# SCH_Hollowed_2025-01-09.net
KiCad netlist of a schematic drawn in EasyEDA
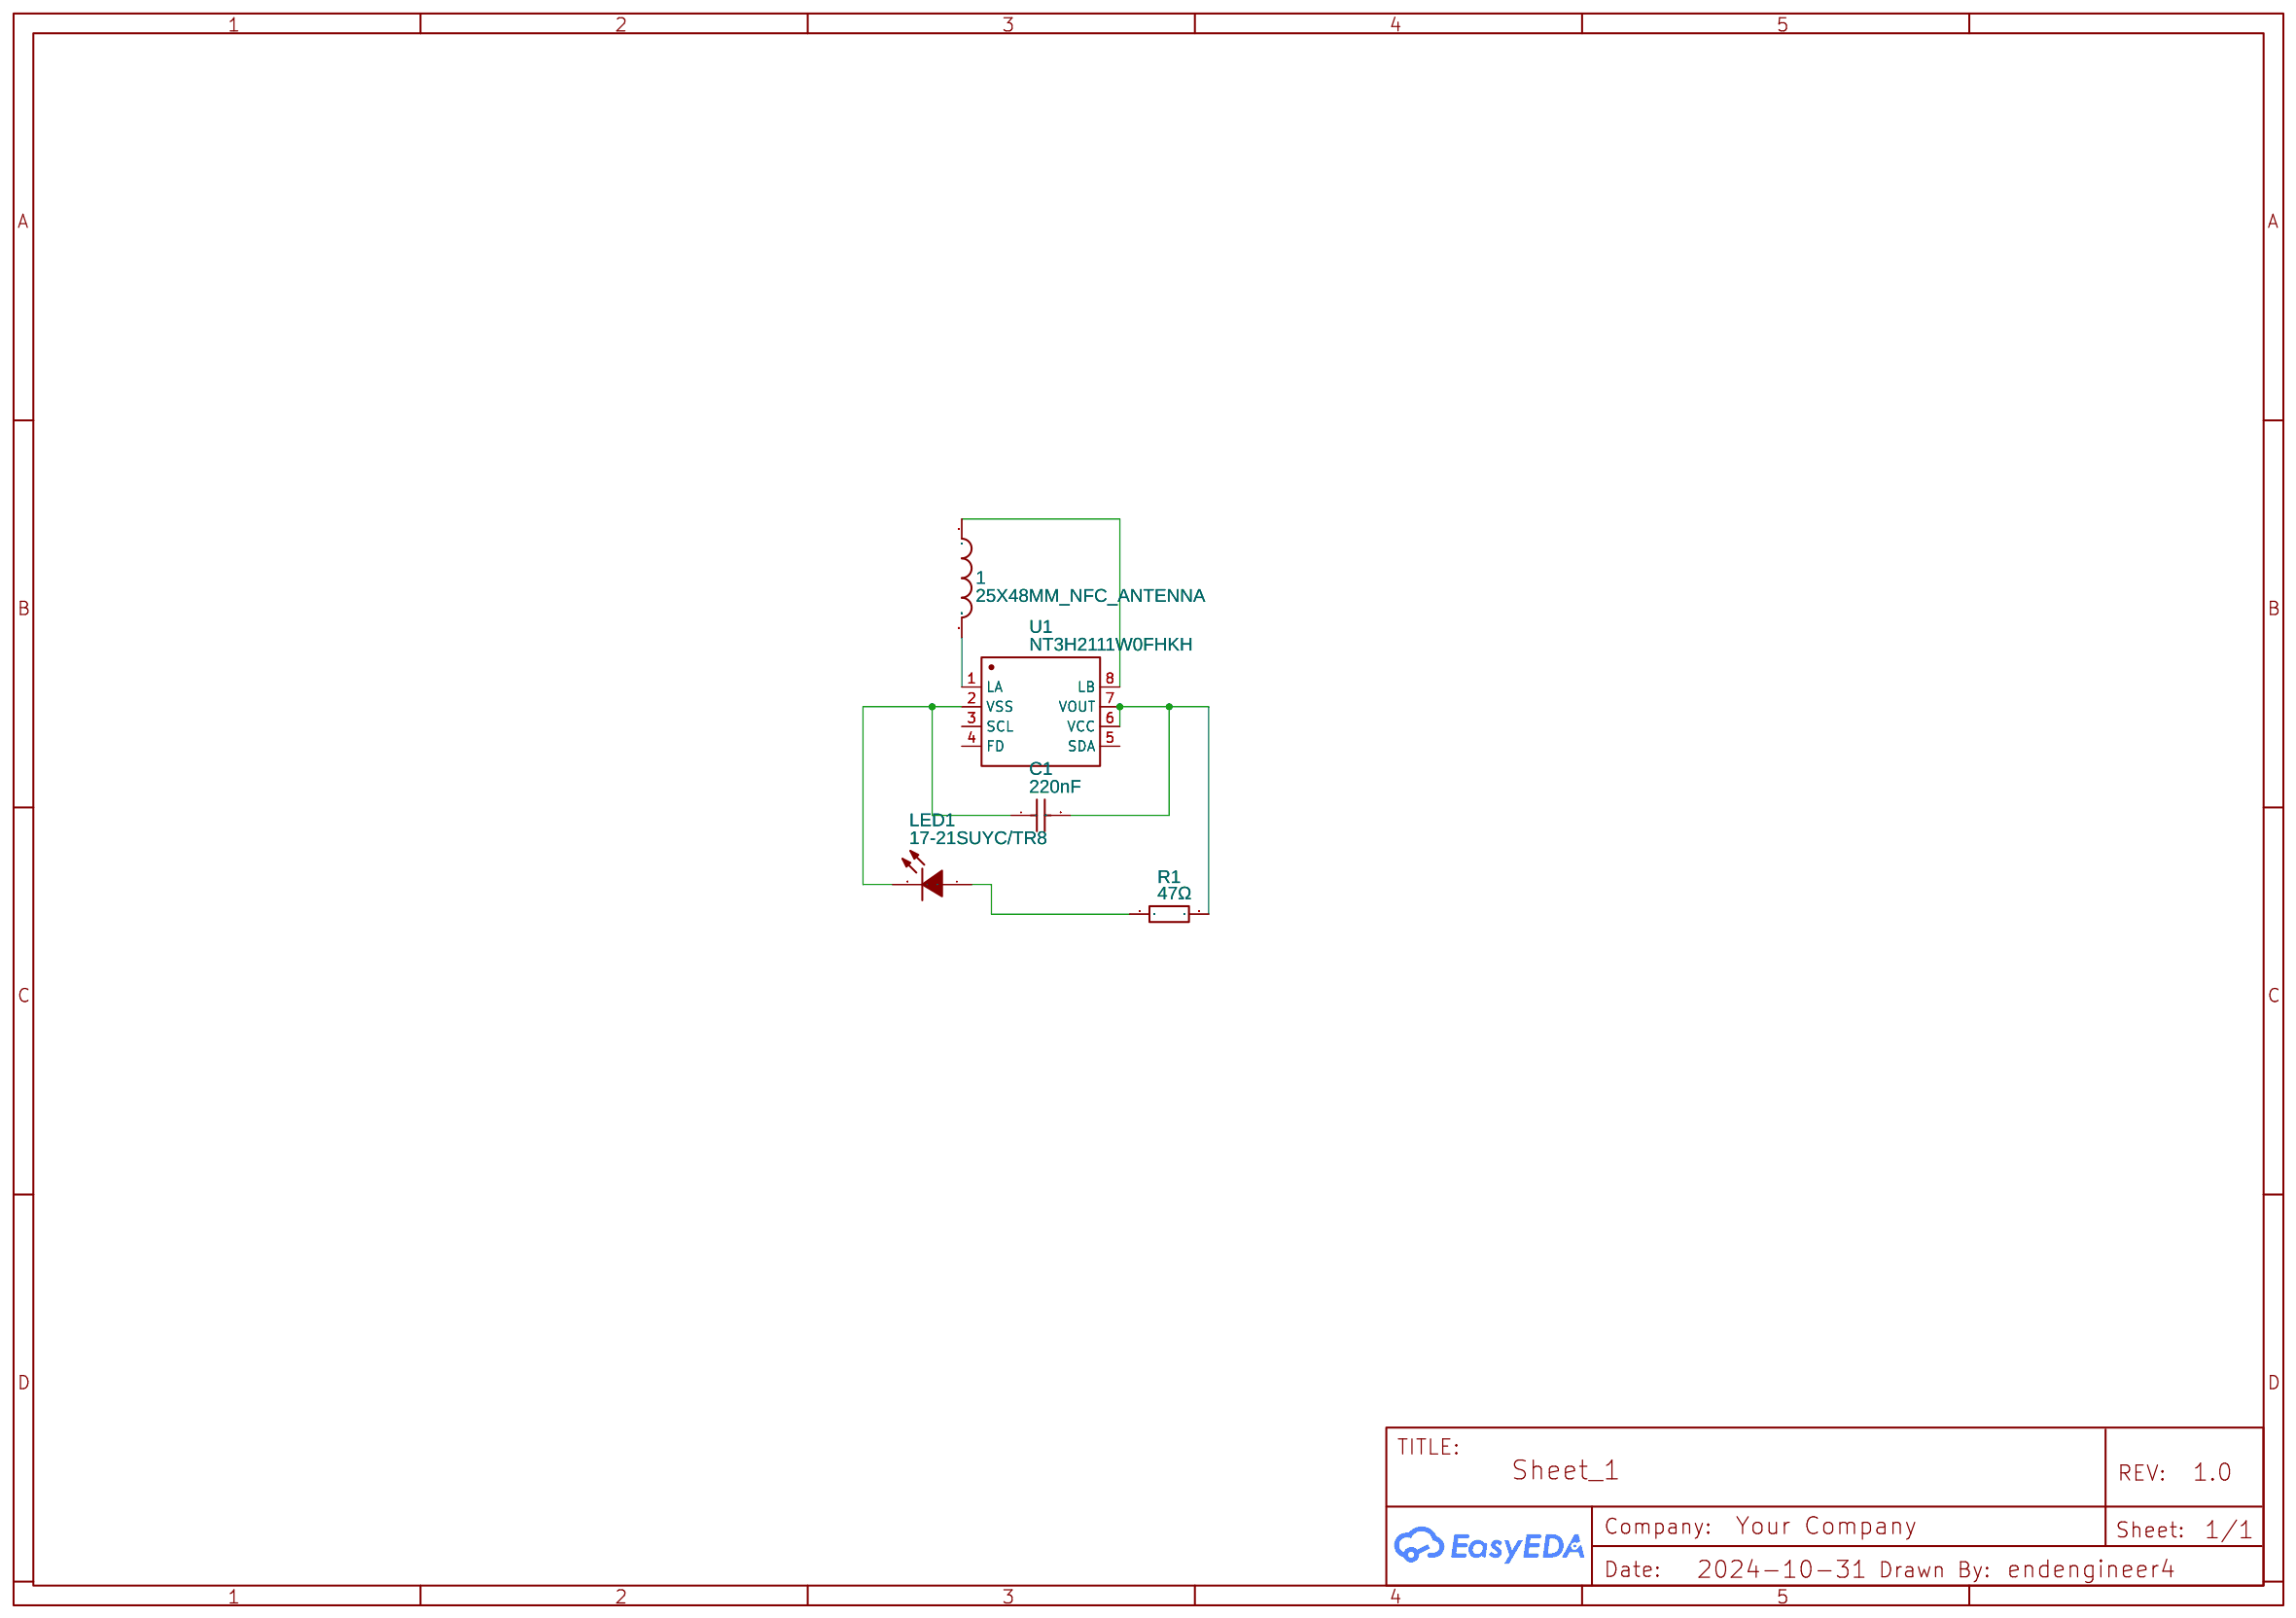
[diagram p0: schematic sheet]

(export (version "E")
  (design (tool "Eeschema 10.0.6"))
  (components
    (comp (ref "1") (value "25X48MM_NFC_ANTENNA") (libsource (lib "") (part "25X48MM_NFC_ANTENNA")))
    (comp (ref "C1")
      (value "220nF")
      (fields
        (field (name "Manufacturer Part") "CL10B224KA8NNNC")
        (field (name "Manufacturer") "SAMSUNG(三星)")
      )
      (libsource (lib "") (part "CL10B224KA8NNNC"))
    )
    (comp (ref "LED1")
      (value "17-21SUYC/TR8")
      (fields (field (name "Manufacturer Part") "KT-0805黄灯") (field (name "Manufacturer") "KENTO"))
      (libsource (lib "") (part "17-21SUYC/TR8"))
    )
    (comp (ref "R1")
      (value "47Ω")
      (fields
        (field (name "Manufacturer Part") "0603WAF470JT5E")
        (field (name "Manufacturer") "UNI-ROYAL(厚声)")
      )
      (libsource (lib "") (part "0603WAF470JT5E"))
    )
    (comp (ref "U1")
      (value "NT3H2111W0FHKH")
      (fields (field (name "Manufacturer") "NXP(恩智浦)"))
      (libsource (lib "") (part "NT3H2111W0FHKH"))
    )
  )
  (nets
    (net (code "1") (name "Net-(LED1-+)") (class "Default")
      (node (ref "LED1") (pin "1") (pinfunction "+_1") (pintype "unspecified"))
      (node (ref "R1") (pin "1") (pinfunction "1_1") (pintype "input"))
    )
    (net (code "2") (name "Net-(LED1--)") (class "Default")
      (node (ref "C1") (pin "1") (pinfunction "1_1") (pintype "input"))
      (node (ref "LED1") (pin "2") (pinfunction "-_2") (pintype "unspecified"))
      (node (ref "U1") (pin "2") (pinfunction "VSS_2") (pintype "unspecified"))
    )
    (net (code "3") (name "Net-(U1-LA)") (class "Default")
      (node (ref "1") (pin "P$2") (pinfunction "P$2_P$2") (pintype "bidirectional"))
      (node (ref "U1") (pin "1") (pinfunction "LA_1") (pintype "unspecified"))
    )
    (net (code "4") (name "Net-(U1-LB)") (class "Default")
      (node (ref "1") (pin "P$1") (pinfunction "P$1_P$1") (pintype "bidirectional"))
      (node (ref "U1") (pin "8") (pinfunction "LB_8") (pintype "unspecified"))
    )
    (net (code "5") (name "Net-(U1-VCC)") (class "Default")
      (node (ref "C1") (pin "2") (pinfunction "2_2") (pintype "input"))
      (node (ref "R1") (pin "2") (pinfunction "2_2") (pintype "input"))
      (node (ref "U1") (pin "6") (pinfunction "VCC_6") (pintype "unspecified"))
      (node (ref "U1") (pin "7") (pinfunction "VOUT_7") (pintype "unspecified"))
    )
    (net (code "6") (name "unconnected-(U1-FD-Pad4)") (class "Default")
      (node (ref "U1") (pin "4") (pinfunction "FD_4") (pintype "unspecified"))
    )
    (net (code "7") (name "unconnected-(U1-SCL-Pad3)") (class "Default")
      (node (ref "U1") (pin "3") (pinfunction "SCL_3") (pintype "unspecified"))
    )
    (net (code "8") (name "unconnected-(U1-SDA-Pad5)") (class "Default")
      (node (ref "U1") (pin "5") (pinfunction "SDA_5") (pintype "unspecified"))
    )
  )
)
